# schematic.net
KiCad netlist of a schematic drawn in EasyEDA
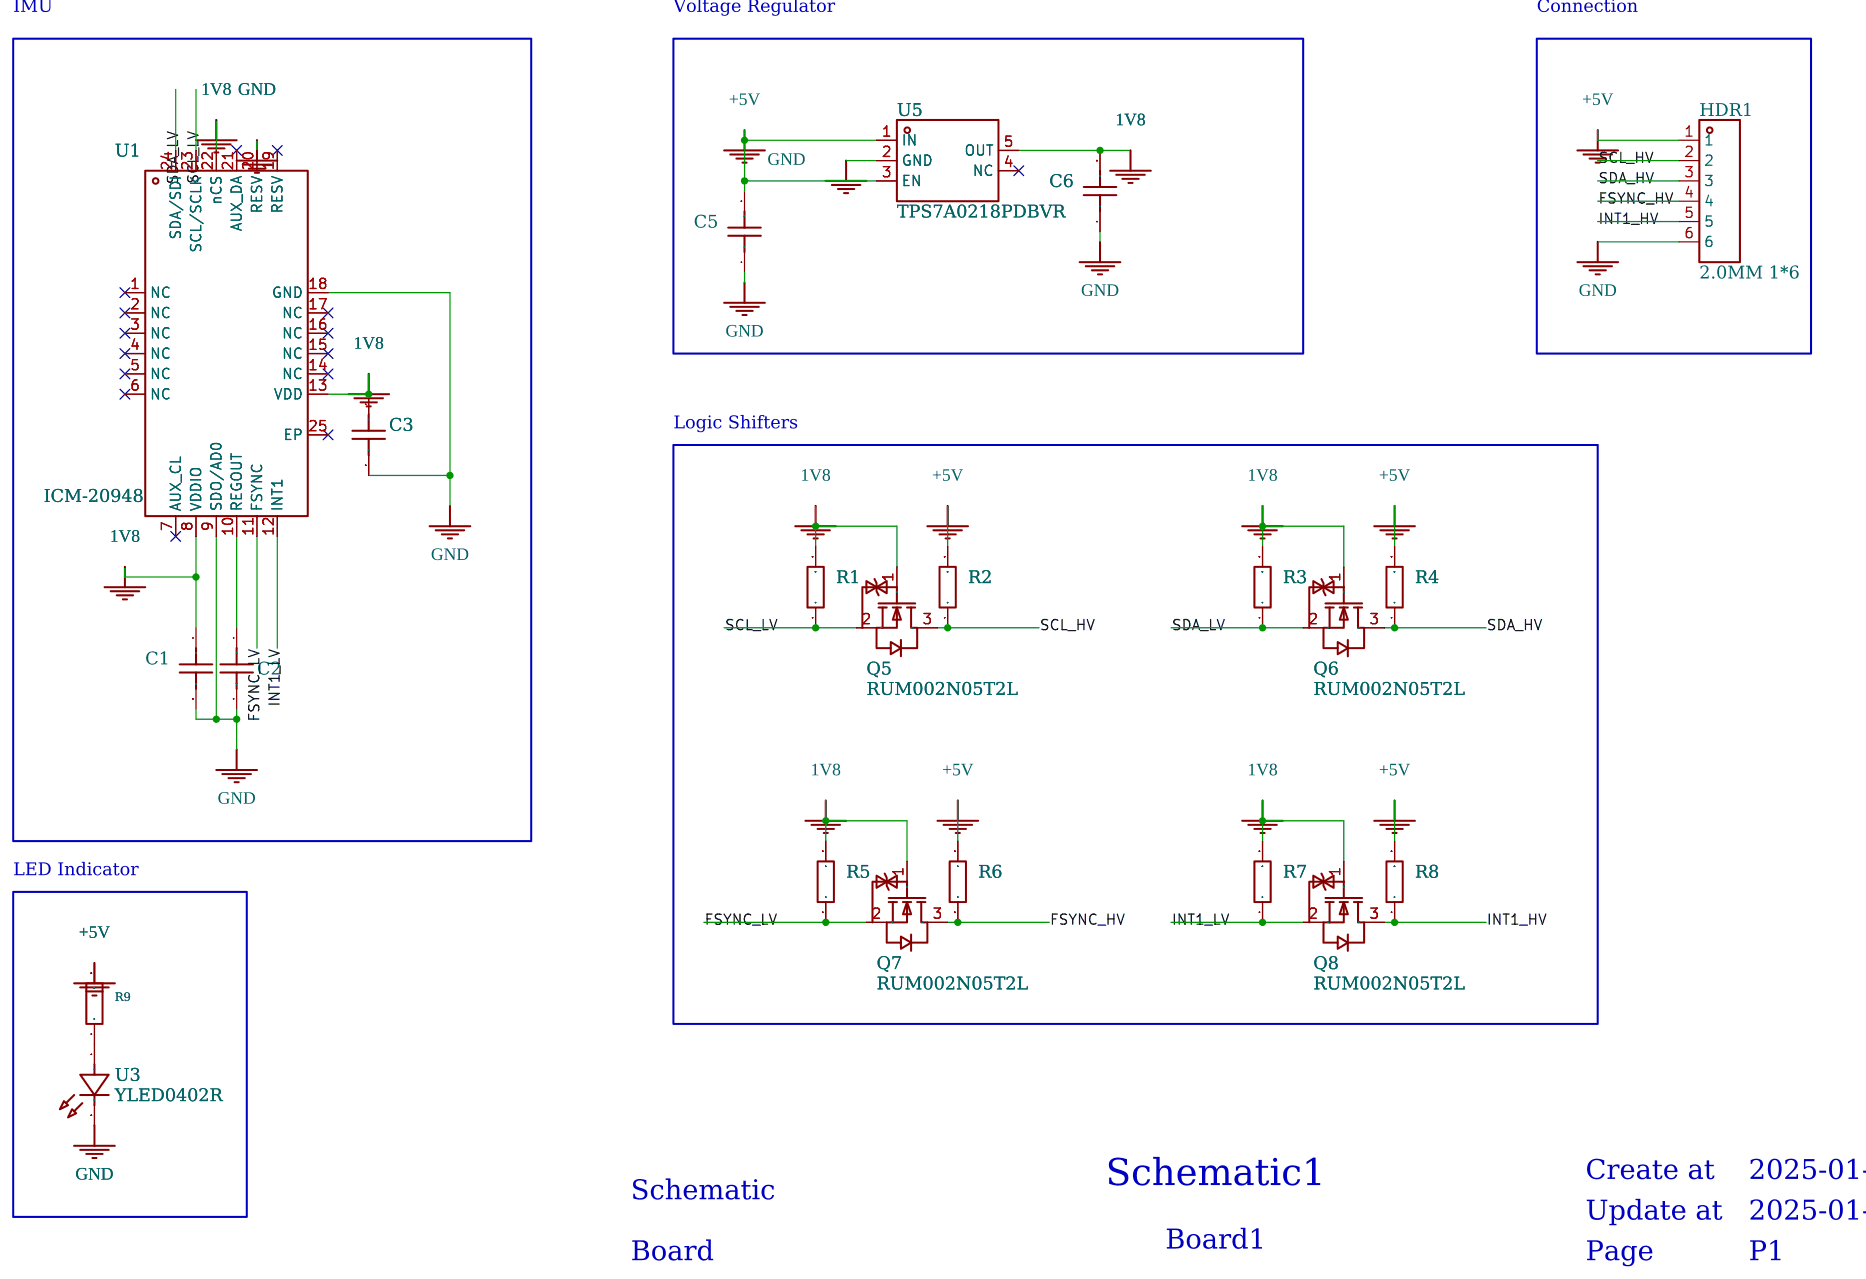
[diagram p0: schematic sheet]

(export (version "E")
  (design (tool "Eeschema 10.0.6"))
  (components
    (comp (ref "C1")
      (value "100nF")
      (fields
        (field (name "Manufacturer Part") "CL05B104KO5NNNC")
        (field (name "Manufacturer") "SAMSUNG(三星)")
      )
      (libsource (lib "") (part "Unknown_265_-450"))
    )
    (comp (ref "C2")
      (value "100nF")
      (fields
        (field (name "Manufacturer Part") "CL05B104KO5NNNC")
        (field (name "Manufacturer") "SAMSUNG(三星)")
      )
      (libsource (lib "") (part "Unknown_285_-450"))
    )
    (comp (ref "C3")
      (value "100nF")
      (fields
        (field (name "Manufacturer Part") "CL05B104KO5NNNC")
        (field (name "Manufacturer") "SAMSUNG(三星)")
      )
      (libsource (lib "") (part "Unknown_350_-565"))
    )
    (comp (ref "C5")
      (value "1uF")
      (fields
        (field (name "Manufacturer Part") "CL05A105KA5NQNC")
        (field (name "Manufacturer") "SAMSUNG(三星)")
      )
      (libsource (lib "") (part "Unknown_535_-665"))
    )
    (comp (ref "C6")
      (value "1uF")
      (fields
        (field (name "Manufacturer Part") "CL05A105KA5NQNC")
        (field (name "Manufacturer") "SAMSUNG(三星)")
      )
      (libsource (lib "") (part "Unknown_710_-685"))
    )
    (comp (ref "HDR1") (value "2.0MM 1*6") (libsource (lib "") (part "Unknown_1015_-685")))
    (comp (ref "Q5")
      (value "RUM002N05T2L")
      (fields (field (name "Manufacturer") "ROHM(罗姆)"))
      (libsource (lib "") (part "Unknown_610_-470"))
    )
    (comp (ref "Q6")
      (value "RUM002N05T2L")
      (fields (field (name "Manufacturer") "ROHM(罗姆)"))
      (libsource (lib "") (part "Unknown_830_-470"))
    )
    (comp (ref "Q7")
      (value "RUM002N05T2L")
      (fields (field (name "Manufacturer") "ROHM(罗姆)"))
      (libsource (lib "") (part "Unknown_615_-325"))
    )
    (comp (ref "Q8")
      (value "RUM002N05T2L")
      (fields (field (name "Manufacturer") "ROHM(罗姆)"))
      (libsource (lib "") (part "Unknown_830_-325"))
    )
    (comp (ref "R1") (value "10K") (libsource (lib "") (part "Unknown_570_-490")))
    (comp (ref "R2") (value "10K") (libsource (lib "") (part "Unknown_635_-490")))
    (comp (ref "R3") (value "10K") (libsource (lib "") (part "Unknown_790_-490")))
    (comp (ref "R4") (value "10K") (libsource (lib "") (part "Unknown_855_-490")))
    (comp (ref "R5") (value "10K") (libsource (lib "") (part "Unknown_575_-345")))
    (comp (ref "R6") (value "10K") (libsource (lib "") (part "Unknown_640_-345")))
    (comp (ref "R7") (value "10K") (libsource (lib "") (part "Unknown_790_-345")))
    (comp (ref "R8") (value "10K") (libsource (lib "") (part "Unknown_855_-345")))
    (comp (ref "R9")
      (value "1kΩ")
      (fields
        (field (name "Manufacturer Part") "0402WGF1001TCE")
        (field (name "Manufacturer") "UNI-ROYAL(厚声)")
      )
      (libsource (lib "") (part "Unknown_215_-285"))
    )
    (comp (ref "U1")
      (value "ICM-20948")
      (fields (field (name "Manufacturer") "TDK InvenSense(应美盛)"))
      (libsource (lib "") (part "Unknown_280_-610"))
    )
    (comp (ref "U3")
      (value "YLED0402R")
      (fields (field (name "Manufacturer") "YONGYUTAI(永裕泰)"))
      (libsource (lib "") (part "Unknown_215_-245"))
    )
    (comp (ref "U5")
      (value "TPS7A0218PDBVR")
      (fields (field (name "Manufacturer") "TI(德州仪器)"))
      (libsource (lib "") (part "Unknown_635_-700"))
    )
  )
  (nets
    (net (code "1") (name "+5V") (class "Default")
      (node (ref "C5") (pin "2") (pinfunction "2_2") (pintype "unspecified"))
      (node (ref "HDR1") (pin "1") (pinfunction "1_1") (pintype "unspecified"))
      (node (ref "R2") (pin "2") (pinfunction "2_2") (pintype "unspecified"))
      (node (ref "R4") (pin "2") (pinfunction "2_2") (pintype "unspecified"))
      (node (ref "R6") (pin "2") (pinfunction "2_2") (pintype "unspecified"))
      (node (ref "R8") (pin "2") (pinfunction "2_2") (pintype "unspecified"))
      (node (ref "R9") (pin "2") (pinfunction "2_2") (pintype "unspecified"))
      (node (ref "U5") (pin "1") (pinfunction "IN_1") (pintype "unspecified"))
      (node (ref "U5") (pin "3") (pinfunction "EN_3") (pintype "unspecified"))
    )
    (net (code "2") (name "/FSYNC_HV") (class "Default")
      (node (ref "HDR1") (pin "4") (pinfunction "4_4") (pintype "unspecified"))
      (node (ref "Q7") (pin "3") (pinfunction "D_3") (pintype "unspecified"))
      (node (ref "R6") (pin "1") (pinfunction "1_1") (pintype "unspecified"))
    )
    (net (code "3") (name "/FSYNC_LV") (class "Default")
      (node (ref "Q7") (pin "2") (pinfunction "S_2") (pintype "unspecified"))
      (node (ref "R5") (pin "1") (pinfunction "1_1") (pintype "unspecified"))
      (node (ref "U1") (pin "11") (pinfunction "FSYNC_11") (pintype "unspecified"))
    )
    (net (code "4") (name "/INT1_HV") (class "Default")
      (node (ref "HDR1") (pin "5") (pinfunction "5_5") (pintype "unspecified"))
      (node (ref "Q8") (pin "3") (pinfunction "D_3") (pintype "unspecified"))
      (node (ref "R8") (pin "1") (pinfunction "1_1") (pintype "unspecified"))
    )
    (net (code "5") (name "/INT1_LV") (class "Default")
      (node (ref "Q8") (pin "2") (pinfunction "S_2") (pintype "unspecified"))
      (node (ref "R7") (pin "1") (pinfunction "1_1") (pintype "unspecified"))
      (node (ref "U1") (pin "12") (pinfunction "INT1_12") (pintype "unspecified"))
    )
    (net (code "6") (name "/SCL_HV") (class "Default")
      (node (ref "HDR1") (pin "2") (pinfunction "2_2") (pintype "unspecified"))
      (node (ref "Q5") (pin "3") (pinfunction "D_3") (pintype "unspecified"))
      (node (ref "R2") (pin "1") (pinfunction "1_1") (pintype "unspecified"))
    )
    (net (code "7") (name "/SCL_LV") (class "Default")
      (node (ref "Q5") (pin "2") (pinfunction "S_2") (pintype "unspecified"))
      (node (ref "R1") (pin "1") (pinfunction "1_1") (pintype "unspecified"))
      (node (ref "U1") (pin "23") (pinfunction "SCL/SCLK_23") (pintype "unspecified"))
    )
    (net (code "8") (name "/SDA_HV") (class "Default")
      (node (ref "HDR1") (pin "3") (pinfunction "3_3") (pintype "unspecified"))
      (node (ref "Q6") (pin "3") (pinfunction "D_3") (pintype "unspecified"))
      (node (ref "R4") (pin "1") (pinfunction "1_1") (pintype "unspecified"))
    )
    (net (code "9") (name "/SDA_LV") (class "Default")
      (node (ref "Q6") (pin "2") (pinfunction "S_2") (pintype "unspecified"))
      (node (ref "R3") (pin "1") (pinfunction "1_1") (pintype "unspecified"))
      (node (ref "U1") (pin "24") (pinfunction "SDA/SDI_24") (pintype "unspecified"))
    )
    (net (code "10") (name "1V8") (class "Default")
      (node (ref "C1") (pin "1") (pinfunction "1_1") (pintype "unspecified"))
      (node (ref "C3") (pin "1") (pinfunction "1_1") (pintype "unspecified"))
      (node (ref "C6") (pin "2") (pinfunction "2_2") (pintype "unspecified"))
      (node (ref "Q5") (pin "1") (pinfunction "G_1") (pintype "unspecified"))
      (node (ref "Q6") (pin "1") (pinfunction "G_1") (pintype "unspecified"))
      (node (ref "Q7") (pin "1") (pinfunction "G_1") (pintype "unspecified"))
      (node (ref "Q8") (pin "1") (pinfunction "G_1") (pintype "unspecified"))
      (node (ref "R1") (pin "2") (pinfunction "2_2") (pintype "unspecified"))
      (node (ref "R3") (pin "2") (pinfunction "2_2") (pintype "unspecified"))
      (node (ref "R5") (pin "2") (pinfunction "2_2") (pintype "unspecified"))
      (node (ref "R7") (pin "2") (pinfunction "2_2") (pintype "unspecified"))
      (node (ref "U1") (pin "13") (pinfunction "VDD_13") (pintype "unspecified"))
      (node (ref "U1") (pin "22") (pinfunction "nCS_22") (pintype "unspecified"))
      (node (ref "U1") (pin "8") (pinfunction "VDDIO_8") (pintype "unspecified"))
      (node (ref "U5") (pin "5") (pinfunction "OUT_5") (pintype "unspecified"))
    )
    (net (code "11") (name "GND") (class "Default")
      (node (ref "C1") (pin "2") (pinfunction "2_2") (pintype "unspecified"))
      (node (ref "C2") (pin "2") (pinfunction "2_2") (pintype "unspecified"))
      (node (ref "C3") (pin "2") (pinfunction "2_2") (pintype "unspecified"))
      (node (ref "C5") (pin "1") (pinfunction "1_1") (pintype "unspecified"))
      (node (ref "C6") (pin "1") (pinfunction "1_1") (pintype "unspecified"))
      (node (ref "HDR1") (pin "6") (pinfunction "6_6") (pintype "unspecified"))
      (node (ref "U1") (pin "18") (pinfunction "GND_18") (pintype "unspecified"))
      (node (ref "U1") (pin "20") (pinfunction "RESV_20") (pintype "unspecified"))
      (node (ref "U1") (pin "9") (pinfunction "SDO/AD0_9") (pintype "unspecified"))
      (node (ref "U3") (pin "2") (pinfunction "K_2") (pintype "unspecified"))
      (node (ref "U5") (pin "2") (pinfunction "GND_2") (pintype "unspecified"))
    )
    (net (code "12") (name "Net-(U1-REGOUT)") (class "Default")
      (node (ref "C2") (pin "1") (pinfunction "1_1") (pintype "unspecified"))
      (node (ref "U1") (pin "10") (pinfunction "REGOUT_10") (pintype "unspecified"))
    )
    (net (code "13") (name "Net-(U3-A)") (class "Default")
      (node (ref "R9") (pin "1") (pinfunction "1_1") (pintype "unspecified"))
      (node (ref "U3") (pin "1") (pinfunction "A_1") (pintype "unspecified"))
    )
    (net (code "14") (name "unconnected-(U1-AUX_CL-Pad7)") (class "Default")
      (node (ref "U1") (pin "7") (pinfunction "AUX_CL_7") (pintype "unspecified+no_connect"))
    )
    (net (code "15") (name "unconnected-(U1-AUX_DA-Pad21)") (class "Default")
      (node (ref "U1") (pin "21") (pinfunction "AUX_DA_21") (pintype "unspecified+no_connect"))
    )
    (net (code "16") (name "unconnected-(U1-EP-Pad25)") (class "Default")
      (node (ref "U1") (pin "25") (pinfunction "EP_25") (pintype "unspecified+no_connect"))
    )
    (net (code "17") (name "unconnected-(U1-NC-Pad1)") (class "Default")
      (node (ref "U1") (pin "1") (pinfunction "NC_1") (pintype "unspecified+no_connect"))
    )
    (net (code "18") (name "unconnected-(U1-NC-Pad2)") (class "Default")
      (node (ref "U1") (pin "2") (pinfunction "NC_2") (pintype "unspecified+no_connect"))
    )
    (net (code "19") (name "unconnected-(U1-NC-Pad3)") (class "Default")
      (node (ref "U1") (pin "3") (pinfunction "NC_3") (pintype "unspecified+no_connect"))
    )
    (net (code "20") (name "unconnected-(U1-NC-Pad4)") (class "Default")
      (node (ref "U1") (pin "4") (pinfunction "NC_4") (pintype "unspecified+no_connect"))
    )
    (net (code "21") (name "unconnected-(U1-NC-Pad5)") (class "Default")
      (node (ref "U1") (pin "5") (pinfunction "NC_5") (pintype "unspecified+no_connect"))
    )
    (net (code "22") (name "unconnected-(U1-NC-Pad6)") (class "Default")
      (node (ref "U1") (pin "6") (pinfunction "NC_6") (pintype "unspecified+no_connect"))
    )
    (net (code "23") (name "unconnected-(U1-NC-Pad14)") (class "Default")
      (node (ref "U1") (pin "14") (pinfunction "NC_14") (pintype "unspecified+no_connect"))
    )
    (net (code "24") (name "unconnected-(U1-NC-Pad15)") (class "Default")
      (node (ref "U1") (pin "15") (pinfunction "NC_15") (pintype "unspecified+no_connect"))
    )
    (net (code "25") (name "unconnected-(U1-NC-Pad16)") (class "Default")
      (node (ref "U1") (pin "16") (pinfunction "NC_16") (pintype "unspecified+no_connect"))
    )
    (net (code "26") (name "unconnected-(U1-NC-Pad17)") (class "Default")
      (node (ref "U1") (pin "17") (pinfunction "NC_17") (pintype "unspecified+no_connect"))
    )
    (net (code "27") (name "unconnected-(U1-RESV-Pad19)") (class "Default")
      (node (ref "U1") (pin "19") (pinfunction "RESV_19") (pintype "unspecified+no_connect"))
    )
    (net (code "28") (name "unconnected-(U5-NC-Pad4)") (class "Default")
      (node (ref "U5") (pin "4") (pinfunction "NC_4") (pintype "unspecified+no_connect"))
    )
  )
)
